# dcy_vca_v1_0_0.net
KiCad netlist of a schematic drawn in EAGLE
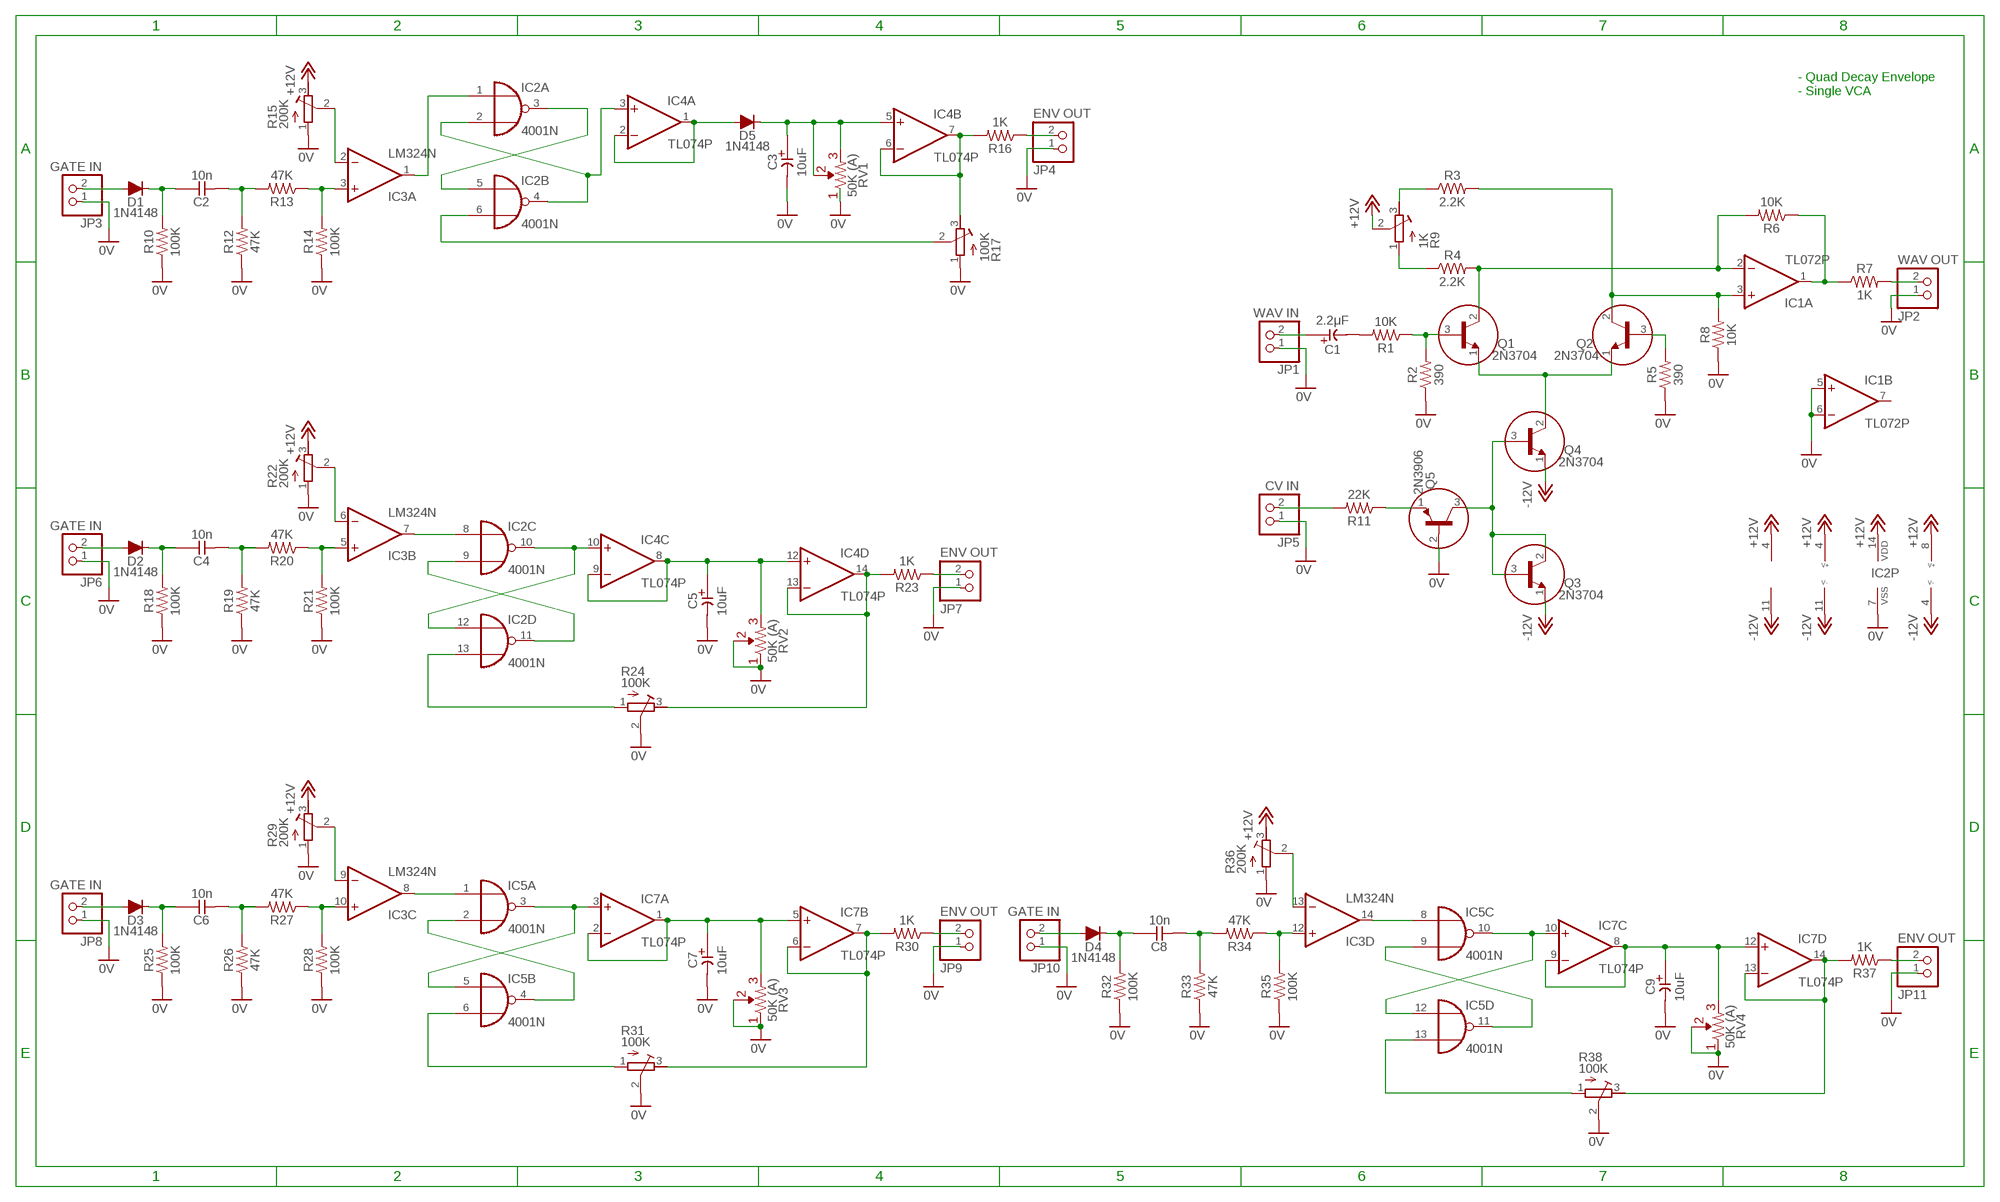
[diagram p0: schematic, sheet 1]

(export (version "E")
  (design (tool "Eeschema 10.0.6"))
  (components
    (comp (ref "C1")
      (value "2.2μF")
      (footprint "eagle-import:E2-5")
      (libsource (lib "eagle-import") (part "CE-USE2-5"))
    )
    (comp (ref "C2")
      (value "10n")
      (footprint "eagle-import:C025-024X044")
      (libsource (lib "eagle-import") (part "CC-US025-024X044"))
    )
    (comp (ref "C3")
      (value "10uF")
      (footprint "eagle-import:E2-5")
      (libsource (lib "eagle-import") (part "CE-USE2-5"))
    )
    (comp (ref "C4")
      (value "10n")
      (footprint "eagle-import:C025-024X044")
      (libsource (lib "eagle-import") (part "CC-US025-024X044"))
    )
    (comp (ref "C5")
      (value "10uF")
      (footprint "eagle-import:E2-5")
      (libsource (lib "eagle-import") (part "CE-USE2-5"))
    )
    (comp (ref "C6")
      (value "10n")
      (footprint "eagle-import:C025-024X044")
      (libsource (lib "eagle-import") (part "CC-US025-024X044"))
    )
    (comp (ref "C7")
      (value "10uF")
      (footprint "eagle-import:E2-5")
      (libsource (lib "eagle-import") (part "CE-USE2-5"))
    )
    (comp (ref "C8")
      (value "10n")
      (footprint "eagle-import:C025-024X044")
      (libsource (lib "eagle-import") (part "CC-US025-024X044"))
    )
    (comp (ref "C9")
      (value "10uF")
      (footprint "eagle-import:E2-5")
      (libsource (lib "eagle-import") (part "CE-USE2-5"))
    )
    (comp (ref "D1")
      (value "1N4148")
      (footprint "eagle-import:DO35-7")
      (libsource (lib "eagle-import") (part "1N4148"))
    )
    (comp (ref "D2")
      (value "1N4148")
      (footprint "eagle-import:DO35-7")
      (libsource (lib "eagle-import") (part "1N4148"))
    )
    (comp (ref "D3")
      (value "1N4148")
      (footprint "eagle-import:DO35-7")
      (libsource (lib "eagle-import") (part "1N4148"))
    )
    (comp (ref "D4")
      (value "1N4148")
      (footprint "eagle-import:DO35-7")
      (libsource (lib "eagle-import") (part "1N4148"))
    )
    (comp (ref "D5")
      (value "1N4148")
      (footprint "eagle-import:DO35-7")
      (libsource (lib "eagle-import") (part "1N4148"))
    )
    (comp (ref "IC1")
      (value "TL072P")
      (footprint "eagle-import:DIL08")
      (libsource (lib "eagle-import") (part "TL072P"))
    )
    (comp (ref "IC2")
      (value "4001N")
      (footprint "eagle-import:DIL14")
      (libsource (lib "eagle-import") (part "4001N"))
    )
    (comp (ref "IC3")
      (value "LM324N")
      (footprint "eagle-import:DIL14")
      (libsource (lib "eagle-import") (part "LM324N"))
    )
    (comp (ref "IC4")
      (value "TL074P")
      (footprint "eagle-import:DIL14")
      (libsource (lib "eagle-import") (part "TL074P"))
    )
    (comp (ref "IC5")
      (value "4001N")
      (footprint "eagle-import:DIL14")
      (libsource (lib "eagle-import") (part "4001N"))
    )
    (comp (ref "IC7")
      (value "TL074P")
      (footprint "eagle-import:DIL14")
      (libsource (lib "eagle-import") (part "TL074P"))
    )
    (comp (ref "JP1")
      (value "WAV IN")
      (footprint "eagle-import:1X02")
      (libsource (lib "eagle-import") (part "PINHD-1X2"))
    )
    (comp (ref "JP2")
      (value "WAV OUT")
      (footprint "eagle-import:1X02")
      (libsource (lib "eagle-import") (part "PINHD-1X2"))
    )
    (comp (ref "JP3")
      (value "GATE IN")
      (footprint "eagle-import:1X02")
      (libsource (lib "eagle-import") (part "PINHD-1X2"))
    )
    (comp (ref "JP4")
      (value "ENV OUT")
      (footprint "eagle-import:1X02")
      (libsource (lib "eagle-import") (part "PINHD-1X2"))
    )
    (comp (ref "JP5")
      (value "CV IN")
      (footprint "eagle-import:1X02")
      (libsource (lib "eagle-import") (part "PINHD-1X2"))
    )
    (comp (ref "JP6")
      (value "GATE IN")
      (footprint "eagle-import:1X02")
      (libsource (lib "eagle-import") (part "PINHD-1X2"))
    )
    (comp (ref "JP7")
      (value "ENV OUT")
      (footprint "eagle-import:1X02")
      (libsource (lib "eagle-import") (part "PINHD-1X2"))
    )
    (comp (ref "JP8")
      (value "GATE IN")
      (footprint "eagle-import:1X02")
      (libsource (lib "eagle-import") (part "PINHD-1X2"))
    )
    (comp (ref "JP9")
      (value "ENV OUT")
      (footprint "eagle-import:1X02")
      (libsource (lib "eagle-import") (part "PINHD-1X2"))
    )
    (comp (ref "JP10")
      (value "GATE IN")
      (footprint "eagle-import:1X02")
      (libsource (lib "eagle-import") (part "PINHD-1X2"))
    )
    (comp (ref "JP11")
      (value "ENV OUT")
      (footprint "eagle-import:1X02")
      (libsource (lib "eagle-import") (part "PINHD-1X2"))
    )
    (comp (ref "Q1")
      (value "2N3704")
      (footprint "eagle-import:TO92")
      (libsource (lib "eagle-import") (part "2N3704"))
    )
    (comp (ref "Q2")
      (value "2N3704")
      (footprint "eagle-import:TO92")
      (libsource (lib "eagle-import") (part "2N3704"))
    )
    (comp (ref "Q3")
      (value "2N3704")
      (footprint "eagle-import:TO92")
      (libsource (lib "eagle-import") (part "2N3704"))
    )
    (comp (ref "Q4")
      (value "2N3704")
      (footprint "eagle-import:TO92")
      (libsource (lib "eagle-import") (part "2N3704"))
    )
    (comp (ref "Q5")
      (value "2N3906")
      (footprint "eagle-import:TO92")
      (libsource (lib "eagle-import") (part "2N3906"))
    )
    (comp (ref "R1")
      (value "10K")
      (footprint "eagle-import:0309_10")
      (libsource (lib "eagle-import") (part "R0309/10"))
    )
    (comp (ref "R2")
      (value "390")
      (footprint "eagle-import:0309_10")
      (libsource (lib "eagle-import") (part "R0309/10"))
    )
    (comp (ref "R3")
      (value "2.2K")
      (footprint "eagle-import:0309_10")
      (libsource (lib "eagle-import") (part "R0309/10"))
    )
    (comp (ref "R4")
      (value "2.2K")
      (footprint "eagle-import:0309_10")
      (libsource (lib "eagle-import") (part "R0309/10"))
    )
    (comp (ref "R5")
      (value "390")
      (footprint "eagle-import:0309_10")
      (libsource (lib "eagle-import") (part "R0309/10"))
    )
    (comp (ref "R6")
      (value "10K")
      (footprint "eagle-import:0309_10")
      (libsource (lib "eagle-import") (part "R0309/10"))
    )
    (comp (ref "R7")
      (value "1K")
      (footprint "eagle-import:0309_10")
      (libsource (lib "eagle-import") (part "R0309/10"))
    )
    (comp (ref "R8")
      (value "10K")
      (footprint "eagle-import:0309_10")
      (libsource (lib "eagle-import") (part "R0309/10"))
    )
    (comp (ref "R9")
      (value "1K")
      (footprint "eagle-import:RTRIM3339P")
      (libsource (lib "eagle-import") (part "R-TRIMM3339P"))
    )
    (comp (ref "R10")
      (value "100K")
      (footprint "eagle-import:0309_10")
      (libsource (lib "eagle-import") (part "R0309/10"))
    )
    (comp (ref "R11")
      (value "22K")
      (footprint "eagle-import:0309_10")
      (libsource (lib "eagle-import") (part "R0309/10"))
    )
    (comp (ref "R12")
      (value "47K")
      (footprint "eagle-import:0309_10")
      (libsource (lib "eagle-import") (part "R0309/10"))
    )
    (comp (ref "R13")
      (value "47K")
      (footprint "eagle-import:0309_10")
      (libsource (lib "eagle-import") (part "R0309/10"))
    )
    (comp (ref "R14")
      (value "100K")
      (footprint "eagle-import:0309_10")
      (libsource (lib "eagle-import") (part "R0309/10"))
    )
    (comp (ref "R15")
      (value "200K")
      (footprint "eagle-import:RTRIM3339P")
      (libsource (lib "eagle-import") (part "R-TRIMM3339P"))
    )
    (comp (ref "R16")
      (value "1K")
      (footprint "eagle-import:0309_10")
      (libsource (lib "eagle-import") (part "R0309/10"))
    )
    (comp (ref "R17")
      (value "100K")
      (footprint "eagle-import:RTRIM3339P")
      (libsource (lib "eagle-import") (part "R-TRIMM3339P"))
    )
    (comp (ref "R18")
      (value "100K")
      (footprint "eagle-import:0309_10")
      (libsource (lib "eagle-import") (part "R0309/10"))
    )
    (comp (ref "R19")
      (value "47K")
      (footprint "eagle-import:0309_10")
      (libsource (lib "eagle-import") (part "R0309/10"))
    )
    (comp (ref "R20")
      (value "47K")
      (footprint "eagle-import:0309_10")
      (libsource (lib "eagle-import") (part "R0309/10"))
    )
    (comp (ref "R21")
      (value "100K")
      (footprint "eagle-import:0309_10")
      (libsource (lib "eagle-import") (part "R0309/10"))
    )
    (comp (ref "R22")
      (value "200K")
      (footprint "eagle-import:RTRIM3339P")
      (libsource (lib "eagle-import") (part "R-TRIMM3339P"))
    )
    (comp (ref "R23")
      (value "1K")
      (footprint "eagle-import:0309_10")
      (libsource (lib "eagle-import") (part "R0309/10"))
    )
    (comp (ref "R24")
      (value "100K")
      (footprint "eagle-import:RTRIM3339P")
      (libsource (lib "eagle-import") (part "R-TRIMM3339P"))
    )
    (comp (ref "R25")
      (value "100K")
      (footprint "eagle-import:0309_10")
      (libsource (lib "eagle-import") (part "R0309/10"))
    )
    (comp (ref "R26")
      (value "47K")
      (footprint "eagle-import:0309_10")
      (libsource (lib "eagle-import") (part "R0309/10"))
    )
    (comp (ref "R27")
      (value "47K")
      (footprint "eagle-import:0309_10")
      (libsource (lib "eagle-import") (part "R0309/10"))
    )
    (comp (ref "R28")
      (value "100K")
      (footprint "eagle-import:0309_10")
      (libsource (lib "eagle-import") (part "R0309/10"))
    )
    (comp (ref "R29")
      (value "200K")
      (footprint "eagle-import:RTRIM3339P")
      (libsource (lib "eagle-import") (part "R-TRIMM3339P"))
    )
    (comp (ref "R30")
      (value "1K")
      (footprint "eagle-import:0309_10")
      (libsource (lib "eagle-import") (part "R0309/10"))
    )
    (comp (ref "R31")
      (value "100K")
      (footprint "eagle-import:RTRIM3339P")
      (libsource (lib "eagle-import") (part "R-TRIMM3339P"))
    )
    (comp (ref "R32")
      (value "100K")
      (footprint "eagle-import:0309_10")
      (libsource (lib "eagle-import") (part "R0309/10"))
    )
    (comp (ref "R33")
      (value "47K")
      (footprint "eagle-import:0309_10")
      (libsource (lib "eagle-import") (part "R0309/10"))
    )
    (comp (ref "R34")
      (value "47K")
      (footprint "eagle-import:0309_10")
      (libsource (lib "eagle-import") (part "R0309/10"))
    )
    (comp (ref "R35")
      (value "100K")
      (footprint "eagle-import:0309_10")
      (libsource (lib "eagle-import") (part "R0309/10"))
    )
    (comp (ref "R36")
      (value "200K")
      (footprint "eagle-import:RTRIM3339P")
      (libsource (lib "eagle-import") (part "R-TRIMM3339P"))
    )
    (comp (ref "R37")
      (value "1K")
      (footprint "eagle-import:0309_10")
      (libsource (lib "eagle-import") (part "R0309/10"))
    )
    (comp (ref "R38")
      (value "100K")
      (footprint "eagle-import:RTRIM3339P")
      (libsource (lib "eagle-import") (part "R-TRIMM3339P"))
    )
    (comp (ref "RV1")
      (value "50K (A)")
      (footprint "eagle-import:R-VAR")
      (libsource (lib "eagle-import") (part "R-VAR"))
    )
    (comp (ref "RV2")
      (value "50K (A)")
      (footprint "eagle-import:R-VAR")
      (libsource (lib "eagle-import") (part "R-VAR"))
    )
    (comp (ref "RV3")
      (value "50K (A)")
      (footprint "eagle-import:R-VAR")
      (libsource (lib "eagle-import") (part "R-VAR"))
    )
    (comp (ref "RV4")
      (value "50K (A)")
      (footprint "eagle-import:R-VAR")
      (libsource (lib "eagle-import") (part "R-VAR"))
    )
  )
  (nets
    (net (code "1") (name "+12V") (class "Default")
      (node (ref "IC1") (pin "8") (pinfunction "V+_8") (pintype "power_in"))
      (node (ref "IC2") (pin "14") (pinfunction "VDD_14") (pintype "power_in"))
      (node (ref "IC3") (pin "4") (pinfunction "V+_4") (pintype "power_in"))
      (node (ref "IC4") (pin "4") (pinfunction "V+_4") (pintype "power_in"))
      (node (ref "R15") (pin "3") (pinfunction "E_3") (pintype "passive"))
      (node (ref "R22") (pin "3") (pinfunction "E_3") (pintype "passive"))
      (node (ref "R29") (pin "3") (pinfunction "E_3") (pintype "passive"))
      (node (ref "R36") (pin "3") (pinfunction "E_3") (pintype "passive"))
      (node (ref "R9") (pin "2") (pinfunction "S_2") (pintype "passive"))
    )
    (net (code "2") (name "-12V") (class "Default")
      (node (ref "IC1") (pin "4") (pinfunction "V-_4") (pintype "power_in"))
      (node (ref "IC3") (pin "11") (pinfunction "V-_11") (pintype "power_in"))
      (node (ref "IC4") (pin "11") (pinfunction "V-_11") (pintype "power_in"))
      (node (ref "Q3") (pin "1") (pinfunction "E_1") (pintype "passive"))
      (node (ref "Q4") (pin "1") (pinfunction "E_1") (pintype "passive"))
    )
    (net (code "3") (name "0V") (class "Default")
      (node (ref "C3") (pin "-") (pinfunction "-_-") (pintype "passive"))
      (node (ref "C5") (pin "-") (pinfunction "-_-") (pintype "passive"))
      (node (ref "C7") (pin "-") (pinfunction "-_-") (pintype "passive"))
      (node (ref "C9") (pin "-") (pinfunction "-_-") (pintype "passive"))
      (node (ref "IC1") (pin "5") (pinfunction "+IN_5") (pintype "input"))
      (node (ref "IC1") (pin "6") (pinfunction "-IN_6") (pintype "input"))
      (node (ref "IC2") (pin "7") (pinfunction "VSS_7") (pintype "power_in"))
      (node (ref "JP1") (pin "1") (pinfunction "1_1") (pintype "passive"))
      (node (ref "JP10") (pin "1") (pinfunction "1_1") (pintype "passive"))
      (node (ref "JP11") (pin "1") (pinfunction "1_1") (pintype "passive"))
      (node (ref "JP2") (pin "1") (pinfunction "1_1") (pintype "passive"))
      (node (ref "JP3") (pin "1") (pinfunction "1_1") (pintype "passive"))
      (node (ref "JP4") (pin "1") (pinfunction "1_1") (pintype "passive"))
      (node (ref "JP5") (pin "1") (pinfunction "1_1") (pintype "passive"))
      (node (ref "JP6") (pin "1") (pinfunction "1_1") (pintype "passive"))
      (node (ref "JP7") (pin "1") (pinfunction "1_1") (pintype "passive"))
      (node (ref "JP8") (pin "1") (pinfunction "1_1") (pintype "passive"))
      (node (ref "JP9") (pin "1") (pinfunction "1_1") (pintype "passive"))
      (node (ref "Q5") (pin "2") (pinfunction "B_2") (pintype "passive"))
      (node (ref "R10") (pin "1") (pinfunction "1_1") (pintype "passive"))
      (node (ref "R12") (pin "1") (pinfunction "1_1") (pintype "passive"))
      (node (ref "R14") (pin "1") (pinfunction "1_1") (pintype "passive"))
      (node (ref "R15") (pin "1") (pinfunction "A_1") (pintype "passive"))
      (node (ref "R17") (pin "1") (pinfunction "A_1") (pintype "passive"))
      (node (ref "R18") (pin "1") (pinfunction "1_1") (pintype "passive"))
      (node (ref "R19") (pin "1") (pinfunction "1_1") (pintype "passive"))
      (node (ref "R2") (pin "1") (pinfunction "1_1") (pintype "passive"))
      (node (ref "R21") (pin "1") (pinfunction "1_1") (pintype "passive"))
      (node (ref "R22") (pin "1") (pinfunction "A_1") (pintype "passive"))
      (node (ref "R24") (pin "2") (pinfunction "S_2") (pintype "passive"))
      (node (ref "R25") (pin "1") (pinfunction "1_1") (pintype "passive"))
      (node (ref "R26") (pin "1") (pinfunction "1_1") (pintype "passive"))
      (node (ref "R28") (pin "1") (pinfunction "1_1") (pintype "passive"))
      (node (ref "R29") (pin "1") (pinfunction "A_1") (pintype "passive"))
      (node (ref "R31") (pin "2") (pinfunction "S_2") (pintype "passive"))
      (node (ref "R32") (pin "1") (pinfunction "1_1") (pintype "passive"))
      (node (ref "R33") (pin "1") (pinfunction "1_1") (pintype "passive"))
      (node (ref "R35") (pin "1") (pinfunction "1_1") (pintype "passive"))
      (node (ref "R36") (pin "1") (pinfunction "A_1") (pintype "passive"))
      (node (ref "R38") (pin "2") (pinfunction "S_2") (pintype "passive"))
      (node (ref "R5") (pin "1") (pinfunction "1_1") (pintype "passive"))
      (node (ref "R8") (pin "1") (pinfunction "1_1") (pintype "passive"))
      (node (ref "RV1") (pin "R1") (pinfunction "1_R1") (pintype "passive"))
      (node (ref "RV2") (pin "R1") (pinfunction "1_R1") (pintype "passive"))
      (node (ref "RV2") (pin "VAR") (pinfunction "P$1_VAR") (pintype "passive"))
      (node (ref "RV3") (pin "R1") (pinfunction "1_R1") (pintype "passive"))
      (node (ref "RV3") (pin "VAR") (pinfunction "P$1_VAR") (pintype "passive"))
      (node (ref "RV4") (pin "R1") (pinfunction "1_R1") (pintype "passive"))
      (node (ref "RV4") (pin "VAR") (pinfunction "P$1_VAR") (pintype "passive"))
    )
    (net (code "4") (name "Net-(C1-Pad+)") (class "Default")
      (node (ref "C1") (pin "+") (pinfunction "+_+") (pintype "passive"))
      (node (ref "JP1") (pin "2") (pinfunction "2_2") (pintype "passive"))
    )
    (net (code "5") (name "Net-(C1-Pad-)") (class "Default")
      (node (ref "C1") (pin "-") (pinfunction "-_-") (pintype "passive"))
      (node (ref "R1") (pin "2") (pinfunction "2_2") (pintype "passive"))
    )
    (net (code "6") (name "Net-(C2-Pad1)") (class "Default")
      (node (ref "C2") (pin "1") (pinfunction "1_1") (pintype "passive"))
      (node (ref "D1") (pin "C") (pinfunction "C_C") (pintype "passive"))
      (node (ref "R10") (pin "2") (pinfunction "2_2") (pintype "passive"))
    )
    (net (code "7") (name "Net-(C2-Pad2)") (class "Default")
      (node (ref "C2") (pin "2") (pinfunction "2_2") (pintype "passive"))
      (node (ref "R12") (pin "2") (pinfunction "2_2") (pintype "passive"))
      (node (ref "R13") (pin "2") (pinfunction "2_2") (pintype "passive"))
    )
    (net (code "8") (name "Net-(C4-Pad1)") (class "Default")
      (node (ref "C4") (pin "1") (pinfunction "1_1") (pintype "passive"))
      (node (ref "D2") (pin "C") (pinfunction "C_C") (pintype "passive"))
      (node (ref "R18") (pin "2") (pinfunction "2_2") (pintype "passive"))
    )
    (net (code "9") (name "Net-(C4-Pad2)") (class "Default")
      (node (ref "C4") (pin "2") (pinfunction "2_2") (pintype "passive"))
      (node (ref "R19") (pin "2") (pinfunction "2_2") (pintype "passive"))
      (node (ref "R20") (pin "2") (pinfunction "2_2") (pintype "passive"))
    )
    (net (code "10") (name "Net-(C6-Pad1)") (class "Default")
      (node (ref "C6") (pin "1") (pinfunction "1_1") (pintype "passive"))
      (node (ref "D3") (pin "C") (pinfunction "C_C") (pintype "passive"))
      (node (ref "R25") (pin "2") (pinfunction "2_2") (pintype "passive"))
    )
    (net (code "11") (name "Net-(C6-Pad2)") (class "Default")
      (node (ref "C6") (pin "2") (pinfunction "2_2") (pintype "passive"))
      (node (ref "R26") (pin "2") (pinfunction "2_2") (pintype "passive"))
      (node (ref "R27") (pin "2") (pinfunction "2_2") (pintype "passive"))
    )
    (net (code "12") (name "Net-(C8-Pad1)") (class "Default")
      (node (ref "C8") (pin "1") (pinfunction "1_1") (pintype "passive"))
      (node (ref "D4") (pin "C") (pinfunction "C_C") (pintype "passive"))
      (node (ref "R32") (pin "2") (pinfunction "2_2") (pintype "passive"))
    )
    (net (code "13") (name "Net-(C8-Pad2)") (class "Default")
      (node (ref "C8") (pin "2") (pinfunction "2_2") (pintype "passive"))
      (node (ref "R33") (pin "2") (pinfunction "2_2") (pintype "passive"))
      (node (ref "R34") (pin "2") (pinfunction "2_2") (pintype "passive"))
    )
    (net (code "14") (name "Net-(D1-PadA)") (class "Default")
      (node (ref "D1") (pin "A") (pinfunction "A_A") (pintype "passive"))
      (node (ref "JP3") (pin "2") (pinfunction "2_2") (pintype "passive"))
    )
    (net (code "15") (name "Net-(D2-PadA)") (class "Default")
      (node (ref "D2") (pin "A") (pinfunction "A_A") (pintype "passive"))
      (node (ref "JP6") (pin "2") (pinfunction "2_2") (pintype "passive"))
    )
    (net (code "16") (name "Net-(D3-PadA)") (class "Default")
      (node (ref "D3") (pin "A") (pinfunction "A_A") (pintype "passive"))
      (node (ref "JP8") (pin "2") (pinfunction "2_2") (pintype "passive"))
    )
    (net (code "17") (name "Net-(D4-PadA)") (class "Default")
      (node (ref "D4") (pin "A") (pinfunction "A_A") (pintype "passive"))
      (node (ref "JP10") (pin "2") (pinfunction "2_2") (pintype "passive"))
    )
    (net (code "18") (name "Net-(IC1A-+IN)") (class "Default")
      (node (ref "IC1") (pin "3") (pinfunction "+IN_3") (pintype "input"))
      (node (ref "Q2") (pin "2") (pinfunction "C_2") (pintype "passive"))
      (node (ref "R3") (pin "2") (pinfunction "2_2") (pintype "passive"))
      (node (ref "R8") (pin "2") (pinfunction "2_2") (pintype "passive"))
    )
    (net (code "19") (name "Net-(IC1A--IN)") (class "Default")
      (node (ref "IC1") (pin "2") (pinfunction "-IN_2") (pintype "input"))
      (node (ref "Q1") (pin "2") (pinfunction "C_2") (pintype "passive"))
      (node (ref "R4") (pin "2") (pinfunction "2_2") (pintype "passive"))
      (node (ref "R6") (pin "2") (pinfunction "2_2") (pintype "passive"))
    )
    (net (code "20") (name "Net-(IC1A-OUT)") (class "Default")
      (node (ref "IC1") (pin "1") (pinfunction "OUT_1") (pintype "output"))
      (node (ref "R6") (pin "1") (pinfunction "1_1") (pintype "passive"))
      (node (ref "R7") (pin "1") (pinfunction "1_1") (pintype "passive"))
    )
    (net (code "21") (name "Net-(IC2A-I0)") (class "Default")
      (node (ref "IC2") (pin "1") (pinfunction "I0_1") (pintype "input"))
      (node (ref "IC3") (pin "1") (pinfunction "OUT_1") (pintype "output"))
    )
    (net (code "22") (name "Net-(IC2A-I1)") (class "Default")
      (node (ref "IC2") (pin "2") (pinfunction "I1_2") (pintype "input"))
      (node (ref "IC2") (pin "4") (pinfunction "O_4") (pintype "output"))
      (node (ref "IC4") (pin "3") (pinfunction "+IN_3") (pintype "input"))
    )
    (net (code "23") (name "Net-(IC2A-O)") (class "Default")
      (node (ref "IC2") (pin "3") (pinfunction "O_3") (pintype "output"))
      (node (ref "IC2") (pin "5") (pinfunction "I0_5") (pintype "input"))
    )
    (net (code "24") (name "Net-(IC2B-I1)") (class "Default")
      (node (ref "IC2") (pin "6") (pinfunction "I1_6") (pintype "input"))
      (node (ref "R17") (pin "2") (pinfunction "S_2") (pintype "passive"))
    )
    (net (code "25") (name "Net-(IC2C-I0)") (class "Default")
      (node (ref "IC2") (pin "8") (pinfunction "I0_8") (pintype "input"))
      (node (ref "IC3") (pin "7") (pinfunction "OUT_7") (pintype "output"))
    )
    (net (code "26") (name "Net-(IC2C-I1)") (class "Default")
      (node (ref "IC2") (pin "11") (pinfunction "O_11") (pintype "output"))
      (node (ref "IC2") (pin "9") (pinfunction "I1_9") (pintype "input"))
    )
    (net (code "27") (name "Net-(IC2C-O)") (class "Default")
      (node (ref "IC2") (pin "10") (pinfunction "O_10") (pintype "output"))
      (node (ref "IC2") (pin "12") (pinfunction "I0_12") (pintype "input"))
      (node (ref "IC4") (pin "10") (pinfunction "+IN_10") (pintype "input"))
    )
    (net (code "28") (name "Net-(IC2D-I1)") (class "Default")
      (node (ref "IC2") (pin "13") (pinfunction "I1_13") (pintype "input"))
      (node (ref "R24") (pin "1") (pinfunction "A_1") (pintype "passive"))
    )
    (net (code "29") (name "Net-(IC3A-+IN)") (class "Default")
      (node (ref "IC3") (pin "3") (pinfunction "+IN_3") (pintype "input"))
      (node (ref "R13") (pin "1") (pinfunction "1_1") (pintype "passive"))
      (node (ref "R14") (pin "2") (pinfunction "2_2") (pintype "passive"))
    )
    (net (code "30") (name "Net-(IC3A--IN)") (class "Default")
      (node (ref "IC3") (pin "2") (pinfunction "-IN_2") (pintype "input"))
      (node (ref "R15") (pin "2") (pinfunction "S_2") (pintype "passive"))
    )
    (net (code "31") (name "Net-(IC3B-+IN)") (class "Default")
      (node (ref "IC3") (pin "5") (pinfunction "+IN_5") (pintype "input"))
      (node (ref "R20") (pin "1") (pinfunction "1_1") (pintype "passive"))
      (node (ref "R21") (pin "2") (pinfunction "2_2") (pintype "passive"))
    )
    (net (code "32") (name "Net-(IC3B--IN)") (class "Default")
      (node (ref "IC3") (pin "6") (pinfunction "-IN_6") (pintype "input"))
      (node (ref "R22") (pin "2") (pinfunction "S_2") (pintype "passive"))
    )
    (net (code "33") (name "Net-(IC3C-+IN)") (class "Default")
      (node (ref "IC3") (pin "10") (pinfunction "+IN_10") (pintype "input"))
      (node (ref "R27") (pin "1") (pinfunction "1_1") (pintype "passive"))
      (node (ref "R28") (pin "2") (pinfunction "2_2") (pintype "passive"))
    )
    (net (code "34") (name "Net-(IC3C--IN)") (class "Default")
      (node (ref "IC3") (pin "9") (pinfunction "-IN_9") (pintype "input"))
      (node (ref "R29") (pin "2") (pinfunction "S_2") (pintype "passive"))
    )
    (net (code "35") (name "Net-(IC3C-OUT)") (class "Default")
      (node (ref "IC3") (pin "8") (pinfunction "OUT_8") (pintype "output"))
      (node (ref "IC5") (pin "1") (pinfunction "I0_1") (pintype "input"))
    )
    (net (code "36") (name "Net-(IC3D-+IN)") (class "Default")
      (node (ref "IC3") (pin "12") (pinfunction "+IN_12") (pintype "input"))
      (node (ref "R34") (pin "1") (pinfunction "1_1") (pintype "passive"))
      (node (ref "R35") (pin "2") (pinfunction "2_2") (pintype "passive"))
    )
    (net (code "37") (name "Net-(IC3D--IN)") (class "Default")
      (node (ref "IC3") (pin "13") (pinfunction "-IN_13") (pintype "input"))
      (node (ref "R36") (pin "2") (pinfunction "S_2") (pintype "passive"))
    )
    (net (code "38") (name "Net-(IC3D-OUT)") (class "Default")
      (node (ref "IC3") (pin "14") (pinfunction "OUT_14") (pintype "output"))
      (node (ref "IC5") (pin "8") (pinfunction "I0_8") (pintype "input"))
    )
    (net (code "39") (name "Net-(IC4A--IN)") (class "Default")
      (node (ref "D5") (pin "A") (pinfunction "A_A") (pintype "passive"))
      (node (ref "IC4") (pin "1") (pinfunction "OUT_1") (pintype "output"))
      (node (ref "IC4") (pin "2") (pinfunction "-IN_2") (pintype "input"))
    )
    (net (code "40") (name "Net-(IC4B-+IN)") (class "Default")
      (node (ref "C3") (pin "+") (pinfunction "+_+") (pintype "passive"))
      (node (ref "D5") (pin "C") (pinfunction "C_C") (pintype "passive"))
      (node (ref "IC4") (pin "5") (pinfunction "+IN_5") (pintype "input"))
      (node (ref "RV1") (pin "R2") (pinfunction "2_R2") (pintype "passive"))
      (node (ref "RV1") (pin "VAR") (pinfunction "P$1_VAR") (pintype "passive"))
    )
    (net (code "41") (name "Net-(IC4B--IN)") (class "Default")
      (node (ref "IC4") (pin "6") (pinfunction "-IN_6") (pintype "input"))
      (node (ref "IC4") (pin "7") (pinfunction "OUT_7") (pintype "output"))
      (node (ref "R16") (pin "2") (pinfunction "2_2") (pintype "passive"))
      (node (ref "R17") (pin "3") (pinfunction "E_3") (pintype "passive"))
    )
    (net (code "42") (name "Net-(IC4C--IN)") (class "Default")
      (node (ref "C5") (pin "+") (pinfunction "+_+") (pintype "passive"))
      (node (ref "IC4") (pin "12") (pinfunction "+IN_12") (pintype "input"))
      (node (ref "IC4") (pin "8") (pinfunction "OUT_8") (pintype "output"))
      (node (ref "IC4") (pin "9") (pinfunction "-IN_9") (pintype "input"))
      (node (ref "RV2") (pin "R2") (pinfunction "2_R2") (pintype "passive"))
    )
    (net (code "43") (name "Net-(IC4D--IN)") (class "Default")
      (node (ref "IC4") (pin "13") (pinfunction "-IN_13") (pintype "input"))
      (node (ref "IC4") (pin "14") (pinfunction "OUT_14") (pintype "output"))
      (node (ref "R23") (pin "2") (pinfunction "2_2") (pintype "passive"))
      (node (ref "R24") (pin "3") (pinfunction "E_3") (pintype "passive"))
    )
    (net (code "44") (name "Net-(IC5A-I1)") (class "Default")
      (node (ref "IC5") (pin "2") (pinfunction "I1_2") (pintype "input"))
      (node (ref "IC5") (pin "4") (pinfunction "O_4") (pintype "output"))
    )
    (net (code "45") (name "Net-(IC5A-O)") (class "Default")
      (node (ref "IC5") (pin "3") (pinfunction "O_3") (pintype "output"))
      (node (ref "IC5") (pin "5") (pinfunction "I0_5") (pintype "input"))
      (node (ref "IC7") (pin "3") (pinfunction "+IN_3") (pintype "input"))
    )
    (net (code "46") (name "Net-(IC5B-I1)") (class "Default")
      (node (ref "IC5") (pin "6") (pinfunction "I1_6") (pintype "input"))
      (node (ref "R31") (pin "1") (pinfunction "A_1") (pintype "passive"))
    )
    (net (code "47") (name "Net-(IC5C-I1)") (class "Default")
      (node (ref "IC5") (pin "11") (pinfunction "O_11") (pintype "output"))
      (node (ref "IC5") (pin "9") (pinfunction "I1_9") (pintype "input"))
    )
    (net (code "48") (name "Net-(IC5C-O)") (class "Default")
      (node (ref "IC5") (pin "10") (pinfunction "O_10") (pintype "output"))
      (node (ref "IC5") (pin "12") (pinfunction "I0_12") (pintype "input"))
      (node (ref "IC7") (pin "10") (pinfunction "+IN_10") (pintype "input"))
    )
    (net (code "49") (name "Net-(IC5D-I1)") (class "Default")
      (node (ref "IC5") (pin "13") (pinfunction "I1_13") (pintype "input"))
      (node (ref "R38") (pin "1") (pinfunction "A_1") (pintype "passive"))
    )
    (net (code "50") (name "Net-(IC7A--IN)") (class "Default")
      (node (ref "C7") (pin "+") (pinfunction "+_+") (pintype "passive"))
      (node (ref "IC7") (pin "1") (pinfunction "OUT_1") (pintype "output"))
      (node (ref "IC7") (pin "2") (pinfunction "-IN_2") (pintype "input"))
      (node (ref "IC7") (pin "5") (pinfunction "+IN_5") (pintype "input"))
      (node (ref "RV3") (pin "R2") (pinfunction "2_R2") (pintype "passive"))
    )
    (net (code "51") (name "Net-(IC7B--IN)") (class "Default")
      (node (ref "IC7") (pin "6") (pinfunction "-IN_6") (pintype "input"))
      (node (ref "IC7") (pin "7") (pinfunction "OUT_7") (pintype "output"))
      (node (ref "R30") (pin "2") (pinfunction "2_2") (pintype "passive"))
      (node (ref "R31") (pin "3") (pinfunction "E_3") (pintype "passive"))
    )
    (net (code "52") (name "Net-(IC7C--IN)") (class "Default")
      (node (ref "C9") (pin "+") (pinfunction "+_+") (pintype "passive"))
      (node (ref "IC7") (pin "12") (pinfunction "+IN_12") (pintype "input"))
      (node (ref "IC7") (pin "8") (pinfunction "OUT_8") (pintype "output"))
      (node (ref "IC7") (pin "9") (pinfunction "-IN_9") (pintype "input"))
      (node (ref "RV4") (pin "R2") (pinfunction "2_R2") (pintype "passive"))
    )
    (net (code "53") (name "Net-(IC7D--IN)") (class "Default")
      (node (ref "IC7") (pin "13") (pinfunction "-IN_13") (pintype "input"))
      (node (ref "IC7") (pin "14") (pinfunction "OUT_14") (pintype "output"))
      (node (ref "R37") (pin "2") (pinfunction "2_2") (pintype "passive"))
      (node (ref "R38") (pin "3") (pinfunction "E_3") (pintype "passive"))
    )
    (net (code "54") (name "Net-(JP2-Pad2)") (class "Default")
      (node (ref "JP2") (pin "2") (pinfunction "2_2") (pintype "passive"))
      (node (ref "R7") (pin "2") (pinfunction "2_2") (pintype "passive"))
    )
    (net (code "55") (name "Net-(JP4-Pad2)") (class "Default")
      (node (ref "JP4") (pin "2") (pinfunction "2_2") (pintype "passive"))
      (node (ref "R16") (pin "1") (pinfunction "1_1") (pintype "passive"))
    )
    (net (code "56") (name "Net-(JP5-Pad2)") (class "Default")
      (node (ref "JP5") (pin "2") (pinfunction "2_2") (pintype "passive"))
      (node (ref "R11") (pin "2") (pinfunction "2_2") (pintype "passive"))
    )
    (net (code "57") (name "Net-(JP7-Pad2)") (class "Default")
      (node (ref "JP7") (pin "2") (pinfunction "2_2") (pintype "passive"))
      (node (ref "R23") (pin "1") (pinfunction "1_1") (pintype "passive"))
    )
    (net (code "58") (name "Net-(JP9-Pad2)") (class "Default")
      (node (ref "JP9") (pin "2") (pinfunction "2_2") (pintype "passive"))
      (node (ref "R30") (pin "1") (pinfunction "1_1") (pintype "passive"))
    )
    (net (code "59") (name "Net-(JP11-Pad2)") (class "Default")
      (node (ref "JP11") (pin "2") (pinfunction "2_2") (pintype "passive"))
      (node (ref "R37") (pin "1") (pinfunction "1_1") (pintype "passive"))
    )
    (net (code "60") (name "Net-(Q1-B)") (class "Default")
      (node (ref "Q1") (pin "3") (pinfunction "B_3") (pintype "passive"))
      (node (ref "R1") (pin "1") (pinfunction "1_1") (pintype "passive"))
      (node (ref "R2") (pin "2") (pinfunction "2_2") (pintype "passive"))
    )
    (net (code "61") (name "Net-(Q1-E)") (class "Default")
      (node (ref "Q1") (pin "1") (pinfunction "E_1") (pintype "passive"))
      (node (ref "Q2") (pin "1") (pinfunction "E_1") (pintype "passive"))
      (node (ref "Q4") (pin "2") (pinfunction "C_2") (pintype "passive"))
    )
    (net (code "62") (name "Net-(Q2-B)") (class "Default")
      (node (ref "Q2") (pin "3") (pinfunction "B_3") (pintype "passive"))
      (node (ref "R5") (pin "2") (pinfunction "2_2") (pintype "passive"))
    )
    (net (code "63") (name "Net-(Q3-B)") (class "Default")
      (node (ref "Q3") (pin "2") (pinfunction "C_2") (pintype "passive"))
      (node (ref "Q3") (pin "3") (pinfunction "B_3") (pintype "passive"))
      (node (ref "Q4") (pin "3") (pinfunction "B_3") (pintype "passive"))
      (node (ref "Q5") (pin "3") (pinfunction "C_3") (pintype "passive"))
    )
    (net (code "64") (name "Net-(Q5-E)") (class "Default")
      (node (ref "Q5") (pin "1") (pinfunction "E_1") (pintype "passive"))
      (node (ref "R11") (pin "1") (pinfunction "1_1") (pintype "passive"))
    )
    (net (code "65") (name "Net-(R9-A)") (class "Default")
      (node (ref "R4") (pin "1") (pinfunction "1_1") (pintype "passive"))
      (node (ref "R9") (pin "1") (pinfunction "A_1") (pintype "passive"))
    )
    (net (code "66") (name "Net-(R9-E)") (class "Default")
      (node (ref "R3") (pin "1") (pinfunction "1_1") (pintype "passive"))
      (node (ref "R9") (pin "3") (pinfunction "E_3") (pintype "passive"))
    )
    (net (code "67") (name "unconnected-(IC1B-OUT-Pad7)") (class "Default")
      (node (ref "IC1") (pin "7") (pinfunction "OUT_7") (pintype "output"))
    )
  )
)
